# CAN_ESC_Adapter_v0_1A.net
KiCad netlist of a schematic drawn in EAGLE
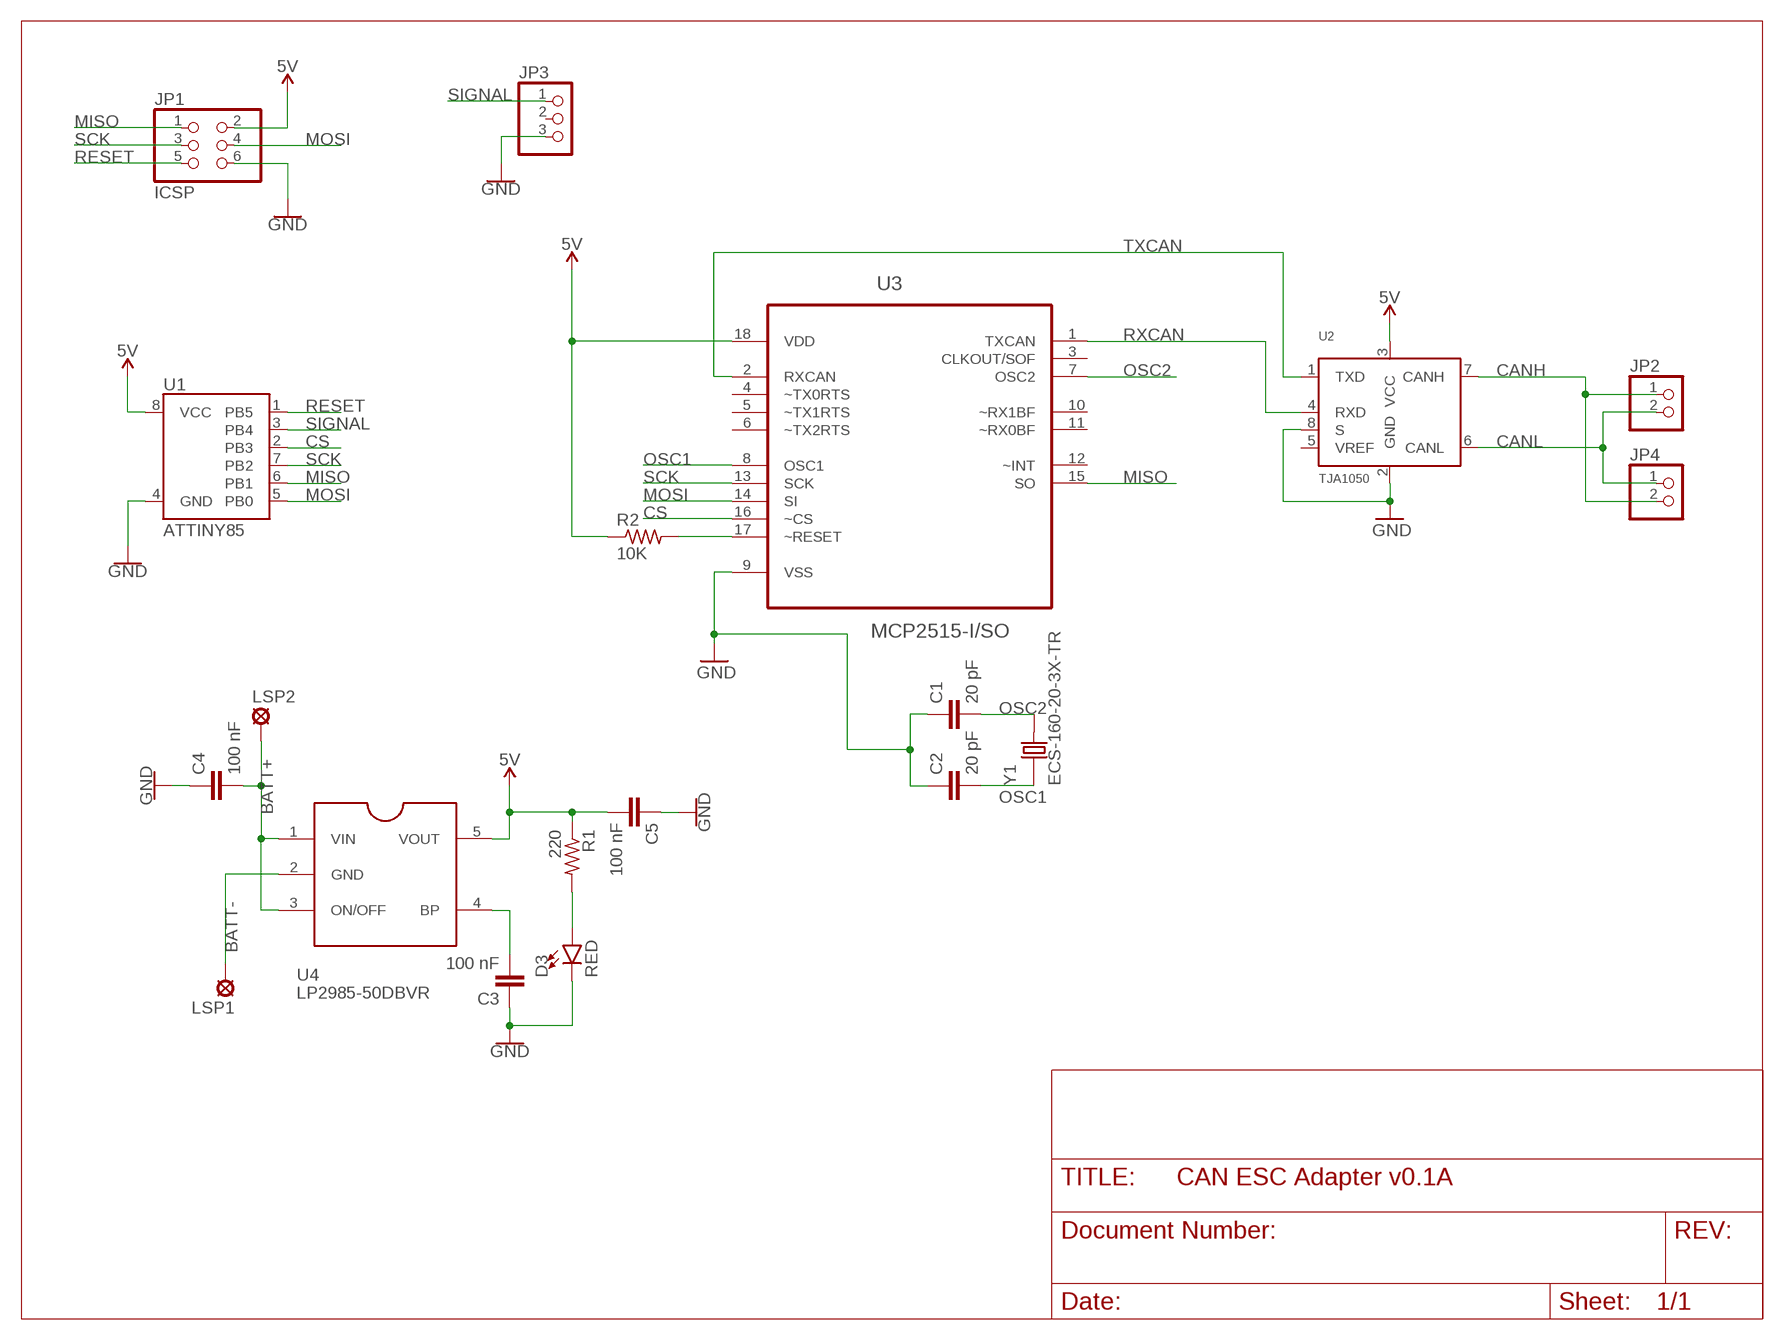
[diagram p0: schematic, sheet 1]

(export (version "E")
  (design (tool "Eeschema 10.0.6"))
  (components
    (comp (ref "C1")
      (value "20 pF")
      (footprint "eagle-import:C0603")
      (libsource (lib "eagle-import") (part "C-EUC0603"))
    )
    (comp (ref "C2")
      (value "20 pF")
      (footprint "eagle-import:C0603")
      (libsource (lib "eagle-import") (part "C-EUC0603"))
    )
    (comp (ref "C3")
      (value "100 nF")
      (footprint "eagle-import:C0603")
      (libsource (lib "eagle-import") (part "C-EUC0603"))
    )
    (comp (ref "C4")
      (value "100 nF")
      (footprint "eagle-import:C0603")
      (libsource (lib "eagle-import") (part "C-EUC0603"))
    )
    (comp (ref "C5")
      (value "100 nF")
      (footprint "eagle-import:C0603")
      (libsource (lib "eagle-import") (part "C-EUC0603"))
    )
    (comp (ref "D3")
      (value "RED")
      (footprint "eagle-import:LED-0603")
      (libsource (lib "eagle-import") (part "LED0603"))
    )
    (comp (ref "JP1")
      (value "ICSP")
      (footprint "eagle-import:2X03")
      (libsource (lib "eagle-import") (part "PINHD-2X3"))
    )
    (comp (ref "JP2")
      (value "PINHD-1X2/90")
      (footprint "eagle-import:1X02_90")
      (libsource (lib "eagle-import") (part "PINHD-1X2/90"))
    )
    (comp (ref "JP3")
      (value "PINHD-1X3/90")
      (footprint "eagle-import:1X03_90")
      (libsource (lib "eagle-import") (part "PINHD-1X3/90"))
    )
    (comp (ref "JP4")
      (value "PINHD-1X2/90")
      (footprint "eagle-import:1X02_90")
      (libsource (lib "eagle-import") (part "PINHD-1X2/90"))
    )
    (comp (ref "LSP1")
      (value "SE14")
      (footprint "eagle-import:SE14")
      (libsource (lib "eagle-import") (part "SE14"))
    )
    (comp (ref "LSP2")
      (value "SE14")
      (footprint "eagle-import:SE14")
      (libsource (lib "eagle-import") (part "SE14"))
    )
    (comp (ref "R1")
      (value "220")
      (footprint "eagle-import:R0603")
      (libsource (lib "eagle-import") (part "R-US_R0603"))
    )
    (comp (ref "R2")
      (value "10K")
      (footprint "eagle-import:R0603")
      (libsource (lib "eagle-import") (part "R-US_R0603"))
    )
    (comp (ref "U1")
      (value "ATTINY85")
      (footprint "eagle-import:ATTINY85")
      (libsource (lib "eagle-import") (part "ATTINY85"))
    )
    (comp (ref "U2")
      (value "TJA1050")
      (footprint "eagle-import:SOT96-1")
      (fields (field (name "DIGI-KEY_PART_NUMBER") "568-10292-1-ND") (field (name "MF") "NXP USA"))
      (libsource (lib "eagle-import") (part "TJA1050"))
    )
    (comp (ref "U3")
      (value "MCP2515-I/SO")
      (footprint "eagle-import:SOIC127P1034X264-18N")
      (fields (field (name "DIGI-KEY_PART_NUMBER") "MCP2515-I/SO-ND") (field (name "MF") "Microchip"))
      (libsource (lib "eagle-import") (part "MCP2515-I/SO"))
    )
    (comp (ref "U4")
      (value "LP2985-50DBVR")
      (footprint "eagle-import:SOT23-5")
      (fields (field (name "MF") "Texas Instruments"))
      (libsource (lib "eagle-import") (part "LP2985-50DBVR"))
    )
    (comp (ref "Y1")
      (value "ECS-160-20-3X-TR")
      (footprint "eagle-import:XTAL_ECS-160-20-3X-TR")
      (fields (field (name "MF") "ECS Inc."))
      (libsource (lib "eagle-import") (part "ECS-160-20-3X-TR"))
    )
  )
  (nets
    (net (code "1") (name "/BATT+") (class "Default")
      (node (ref "C4") (pin "2") (pinfunction "2_2") (pintype "passive"))
      (node (ref "LSP2") (pin "MP") (pinfunction "MP_MP") (pintype "passive"))
      (node (ref "U4") (pin "1") (pinfunction "VIN_1") (pintype "input"))
      (node (ref "U4") (pin "3") (pinfunction "ON/OFF_3") (pintype "input"))
    )
    (net (code "2") (name "/BATT-") (class "Default")
      (node (ref "LSP1") (pin "MP") (pinfunction "MP_MP") (pintype "passive"))
      (node (ref "U4") (pin "2") (pinfunction "GND_2") (pintype "passive"))
    )
    (net (code "3") (name "/CANH") (class "Default")
      (node (ref "JP2") (pin "1") (pinfunction "1_1") (pintype "passive"))
      (node (ref "JP4") (pin "2") (pinfunction "2_2") (pintype "passive"))
      (node (ref "U2") (pin "7") (pinfunction "CANH_7") (pintype "bidirectional"))
    )
    (net (code "4") (name "/CANL") (class "Default")
      (node (ref "JP2") (pin "2") (pinfunction "2_2") (pintype "passive"))
      (node (ref "JP4") (pin "1") (pinfunction "1_1") (pintype "passive"))
      (node (ref "U2") (pin "6") (pinfunction "CANL_6") (pintype "bidirectional"))
    )
    (net (code "5") (name "/CS") (class "Default")
      (node (ref "U1") (pin "2") (pinfunction "PB3_2") (pintype "bidirectional"))
      (node (ref "U3") (pin "16") (pinfunction "~{CS}_16") (pintype "input"))
    )
    (net (code "6") (name "/MISO") (class "Default")
      (node (ref "JP1") (pin "1") (pinfunction "1_1") (pintype "passive"))
      (node (ref "U1") (pin "6") (pinfunction "PB1_6") (pintype "bidirectional"))
      (node (ref "U3") (pin "15") (pinfunction "SO_15") (pintype "output"))
    )
    (net (code "7") (name "/MOSI") (class "Default")
      (node (ref "JP1") (pin "4") (pinfunction "4_4") (pintype "passive"))
      (node (ref "U1") (pin "5") (pinfunction "PB0_5") (pintype "bidirectional"))
      (node (ref "U3") (pin "14") (pinfunction "SI_14") (pintype "input"))
    )
    (net (code "8") (name "/OSC1") (class "Default")
      (node (ref "C2") (pin "2") (pinfunction "2_2") (pintype "passive"))
      (node (ref "U3") (pin "8") (pinfunction "OSC1_8") (pintype "input"))
      (node (ref "Y1") (pin "1") (pinfunction "1_1") (pintype "passive"))
    )
    (net (code "9") (name "/OSC2") (class "Default")
      (node (ref "C1") (pin "2") (pinfunction "2_2") (pintype "passive"))
      (node (ref "U3") (pin "7") (pinfunction "OSC2_7") (pintype "output"))
      (node (ref "Y1") (pin "2") (pinfunction "2_2") (pintype "passive"))
    )
    (net (code "10") (name "/RESET") (class "Default")
      (node (ref "JP1") (pin "5") (pinfunction "5_5") (pintype "passive"))
      (node (ref "U1") (pin "1") (pinfunction "PB5_1") (pintype "bidirectional"))
    )
    (net (code "11") (name "/RXCAN") (class "Default")
      (node (ref "U2") (pin "4") (pinfunction "RXD_4") (pintype "bidirectional"))
      (node (ref "U3") (pin "1") (pinfunction "TXCAN_1") (pintype "output"))
    )
    (net (code "12") (name "/SCK") (class "Default")
      (node (ref "JP1") (pin "3") (pinfunction "3_3") (pintype "passive"))
      (node (ref "U1") (pin "7") (pinfunction "PB2_7") (pintype "bidirectional"))
      (node (ref "U3") (pin "13") (pinfunction "SCK_13") (pintype "input"))
    )
    (net (code "13") (name "/SIGNAL") (class "Default")
      (node (ref "JP3") (pin "1") (pinfunction "1_1") (pintype "passive"))
      (node (ref "U1") (pin "3") (pinfunction "PB4_3") (pintype "bidirectional"))
    )
    (net (code "14") (name "/TXCAN") (class "Default")
      (node (ref "U2") (pin "1") (pinfunction "TXD_1") (pintype "output"))
      (node (ref "U3") (pin "2") (pinfunction "RXCAN_2") (pintype "input"))
    )
    (net (code "15") (name "5V") (class "Default")
      (node (ref "C5") (pin "2") (pinfunction "2_2") (pintype "passive"))
      (node (ref "JP1") (pin "2") (pinfunction "2_2") (pintype "passive"))
      (node (ref "R1") (pin "1") (pinfunction "1_1") (pintype "passive"))
      (node (ref "R2") (pin "1") (pinfunction "1_1") (pintype "passive"))
      (node (ref "U1") (pin "8") (pinfunction "VCC_8") (pintype "bidirectional"))
      (node (ref "U2") (pin "3") (pinfunction "VCC_3") (pintype "bidirectional"))
      (node (ref "U3") (pin "18") (pinfunction "VDD_18") (pintype "power_in"))
      (node (ref "U4") (pin "5") (pinfunction "VOUT_5") (pintype "output"))
    )
    (net (code "16") (name "GND") (class "Default")
      (node (ref "C1") (pin "1") (pinfunction "1_1") (pintype "passive"))
      (node (ref "C2") (pin "1") (pinfunction "1_1") (pintype "passive"))
      (node (ref "C3") (pin "1") (pinfunction "1_1") (pintype "passive"))
      (node (ref "C4") (pin "1") (pinfunction "1_1") (pintype "passive"))
      (node (ref "C5") (pin "1") (pinfunction "1_1") (pintype "passive"))
      (node (ref "D3") (pin "C") (pinfunction "C_C") (pintype "passive"))
      (node (ref "JP1") (pin "6") (pinfunction "6_6") (pintype "passive"))
      (node (ref "JP3") (pin "3") (pinfunction "3_3") (pintype "passive"))
      (node (ref "U1") (pin "4") (pinfunction "GND_4") (pintype "bidirectional"))
      (node (ref "U2") (pin "2") (pinfunction "GND_2") (pintype "bidirectional"))
      (node (ref "U2") (pin "8") (pinfunction "S_8") (pintype "power_in"))
      (node (ref "U3") (pin "9") (pinfunction "VSS_9") (pintype "power_in"))
    )
    (net (code "17") (name "Net-(D3-PadA)") (class "Default")
      (node (ref "D3") (pin "A") (pinfunction "A_A") (pintype "passive"))
      (node (ref "R1") (pin "2") (pinfunction "2_2") (pintype "passive"))
    )
    (net (code "18") (name "Net-(U3-~{RESET})") (class "Default")
      (node (ref "R2") (pin "2") (pinfunction "2_2") (pintype "passive"))
      (node (ref "U3") (pin "17") (pinfunction "~{RESET}_17") (pintype "input"))
    )
    (net (code "19") (name "Net-(U4-BP)") (class "Default")
      (node (ref "C3") (pin "2") (pinfunction "2_2") (pintype "passive"))
      (node (ref "U4") (pin "4") (pinfunction "BP_4") (pintype "output"))
    )
    (net (code "20") (name "unconnected-(JP3-Pad2)") (class "Default")
      (node (ref "JP3") (pin "2") (pinfunction "2_2") (pintype "passive"))
    )
    (net (code "21") (name "unconnected-(U2-VREF-Pad5)") (class "Default")
      (node (ref "U2") (pin "5") (pinfunction "VREF_5") (pintype "passive"))
    )
    (net (code "22") (name "unconnected-(U3-CLKOUT{slash}SOF-Pad3)") (class "Default")
      (node (ref "U3") (pin "3") (pinfunction "CLKOUT/SOF_3") (pintype "output"))
    )
    (net (code "23") (name "unconnected-(U3-~{INT}-Pad12)") (class "Default")
      (node (ref "U3") (pin "12") (pinfunction "~{INT}_12") (pintype "output"))
    )
    (net (code "24") (name "unconnected-(U3-~{RX0BF}-Pad11)") (class "Default")
      (node (ref "U3") (pin "11") (pinfunction "~{RX0BF}_11") (pintype "output"))
    )
    (net (code "25") (name "unconnected-(U3-~{RX1BF}-Pad10)") (class "Default")
      (node (ref "U3") (pin "10") (pinfunction "~{RX1BF}_10") (pintype "output"))
    )
    (net (code "26") (name "unconnected-(U3-~{TX0RTS}-Pad4)") (class "Default")
      (node (ref "U3") (pin "4") (pinfunction "~{TX0RTS}_4") (pintype "input"))
    )
    (net (code "27") (name "unconnected-(U3-~{TX1RTS}-Pad5)") (class "Default")
      (node (ref "U3") (pin "5") (pinfunction "~{TX1RTS}_5") (pintype "input"))
    )
    (net (code "28") (name "unconnected-(U3-~{TX2RTS}-Pad6)") (class "Default")
      (node (ref "U3") (pin "6") (pinfunction "~{TX2RTS}_6") (pintype "input"))
    )
  )
)
